# MecanumDrone_SchematicV1.net
KiCad netlist of a schematic drawn in EasyEDA Pro
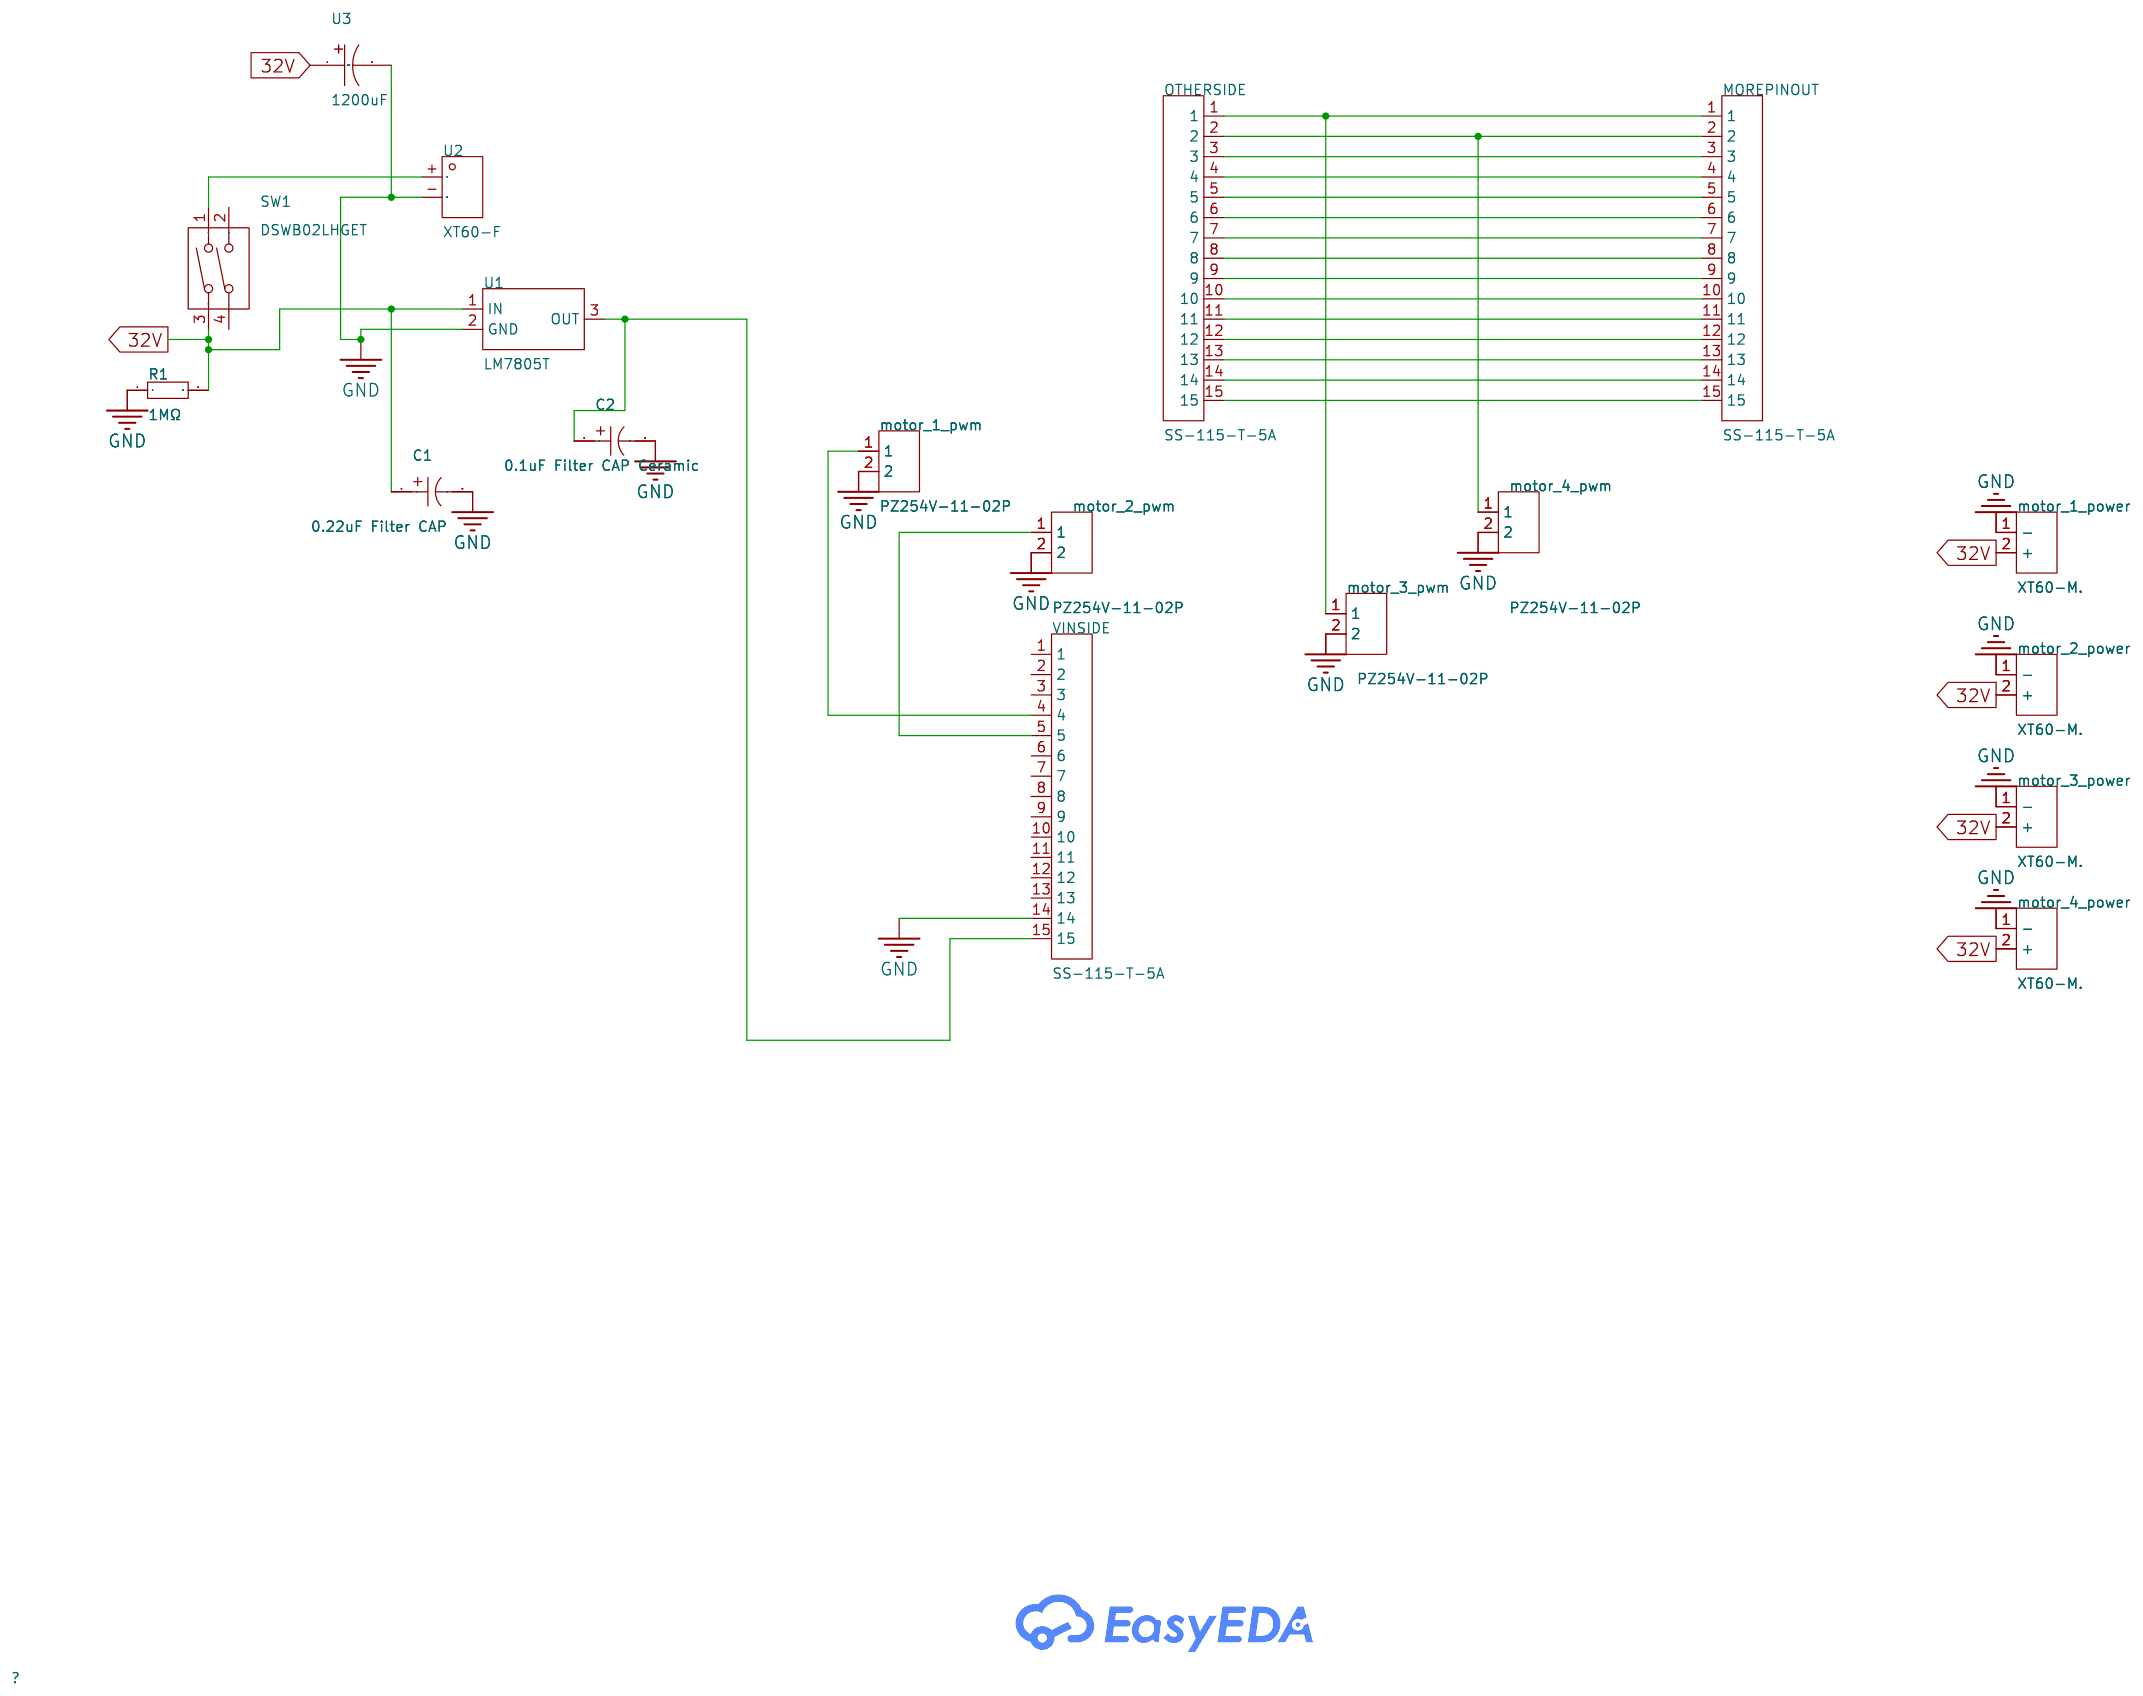
[diagram p0: schematic sheet]

(export (version "E")
  (design (tool "Eeschema 10.0.6"))
  (components
    (comp (ref "C1")
      (value "0.22uF Filter CAP")
      (footprint "easyedapro:CAP-TH_BD6.0-P2.50-D0.5-FD")
      (fields (field (name "Manufacturer Part") "KM1E101M0611") (field (name "Manufacturer") "ROQANG(容强)"))
      (libsource (lib "easyedapro") (part "KM1E101M0611"))
    )
    (comp (ref "C2")
      (value "0.1uF Filter CAP Ceramic")
      (footprint "easyedapro:CAP-TH_BD6.0-P2.50-D0.5-FD")
      (fields (field (name "Manufacturer Part") "KM1E101M0611") (field (name "Manufacturer") "ROQANG(容强)"))
      (libsource (lib "easyedapro") (part "KM1E101M0611"))
    )
    (comp (ref "MOREPINOUT")
      (value "SS-115-T-5A")
      (footprint "easyedapro:HDR-TH_15P-SS-115-T-5A")
      (fields (field (name "Manufacturer") "SAMTEC"))
      (libsource (lib "easyedapro") (part "SS-115-T-5A"))
    )
    (comp (ref "motor_1_power")
      (value "XT60-M.")
      (footprint "easyedapro:CONN-TH_XT60")
      (fields (field (name "Manufacturer") "AMASS(艾迈斯)"))
      (libsource (lib "easyedapro") (part "XT60"))
    )
    (comp (ref "motor_1_pwm")
      (value "PZ254V-11-02P")
      (footprint "easyedapro:HDR-TH_2P-P2.54-V-M")
      (fields (field (name "Manufacturer") "XFCN(兴飞)"))
      (libsource (lib "easyedapro") (part "PZ254V-11-02P"))
    )
    (comp (ref "motor_2_power")
      (value "XT60-M.")
      (footprint "easyedapro:CONN-TH_XT60")
      (fields (field (name "Manufacturer") "AMASS(艾迈斯)"))
      (libsource (lib "easyedapro") (part "XT60"))
    )
    (comp (ref "motor_2_pwm")
      (value "PZ254V-11-02P")
      (footprint "easyedapro:HDR-TH_2P-P2.54-V-M")
      (fields (field (name "Manufacturer") "XFCN(兴飞)"))
      (libsource (lib "easyedapro") (part "PZ254V-11-02P"))
    )
    (comp (ref "motor_3_power")
      (value "XT60-M.")
      (footprint "easyedapro:CONN-TH_XT60")
      (fields (field (name "Manufacturer") "AMASS(艾迈斯)"))
      (libsource (lib "easyedapro") (part "XT60"))
    )
    (comp (ref "motor_3_pwm")
      (value "PZ254V-11-02P")
      (footprint "easyedapro:HDR-TH_2P-P2.54-V-M")
      (fields (field (name "Manufacturer") "XFCN(兴飞)"))
      (libsource (lib "easyedapro") (part "PZ254V-11-02P"))
    )
    (comp (ref "motor_4_power")
      (value "XT60-M.")
      (footprint "easyedapro:CONN-TH_XT60")
      (fields (field (name "Manufacturer") "AMASS(艾迈斯)"))
      (libsource (lib "easyedapro") (part "XT60"))
    )
    (comp (ref "motor_4_pwm")
      (value "PZ254V-11-02P")
      (footprint "easyedapro:HDR-TH_2P-P2.54-V-M")
      (fields (field (name "Manufacturer") "XFCN(兴飞)"))
      (libsource (lib "easyedapro") (part "PZ254V-11-02P"))
    )
    (comp (ref "OTHERSIDE")
      (value "SS-115-T-5A")
      (footprint "easyedapro:HDR-TH_15P-SS-115-T-5A")
      (fields (field (name "Manufacturer") "SAMTEC"))
      (libsource (lib "easyedapro") (part "SS-115-T-5A"))
    )
    (comp (ref "R1")
      (value "1MΩ")
      (footprint "easyedapro:RES-TH_BD2.2-L6.5-P10.50-D0.6")
      (fields
        (field (name "Manufacturer Part") "RN1/2WS1MΩFT/BA1")
        (field (name "Manufacturer") "Tyohm(幸亚电阻)")
      )
      (libsource (lib "easyedapro") (part "RN1/2WS1MΩFT/BA1"))
    )
    (comp (ref "SW1")
      (value "DSWB02LHGET")
      (footprint "easyedapro:SW-TH_DSWB02LHGET")
      (description "Type:Slide, Rocked Circuit:SPST Number of Positions:2 Lead Pitch:2.54mm Operating Life:- Color:Red")
      (fields (field (name "Manufacturer") "YE"))
      (libsource (lib "easyedapro") (part "DSWB02LHGET"))
    )
    (comp (ref "U1")
      (value "LM7805T")
      (footprint "easyedapro:TO-220-3_L10.0-W4.5-P2.54-L-1")
      (fields (field (name "Manufacturer") "HTC"))
      (libsource (lib "easyedapro") (part "LM7805T_C36350857"))
    )
    (comp (ref "U2")
      (value "XT60-F")
      (footprint "easyedapro:CONN-TH_XT60PB-F")
      (fields (field (name "Manufacturer") "AMASS(艾迈斯)"))
      (libsource (lib "easyedapro") (part "XT60-F"))
    )
    (comp (ref "U3")
      (value "1200uF")
      (footprint "easyedapro:CAP-TH_BD30.0-P10.00-D2.3-FD")
      (fields (field (name "Manufacturer Part") "B43305B2128M67") (field (name "Manufacturer") "TDK"))
      (libsource (lib "easyedapro") (part "B43305B2128M67"))
    )
    (comp (ref "VINSIDE")
      (value "SS-115-T-5A")
      (footprint "easyedapro:HDR-TH_15P-SS-115-T-5A")
      (fields (field (name "Manufacturer") "SAMTEC"))
      (libsource (lib "easyedapro") (part "SS-115-T-5A"))
    )
  )
  (nets
    (net (code "1") (name "32V") (class "Default")
      (node (ref "C1") (pin "1") (pinfunction "1_1") (pintype "input"))
      (node (ref "R1") (pin "2") (pinfunction "2_2") (pintype "unspecified"))
      (node (ref "SW1") (pin "3") (pinfunction "3_3") (pintype "unspecified"))
      (node (ref "U1") (pin "1") (pinfunction "IN_1") (pintype "unspecified"))
      (node (ref "U3") (pin "1") (pinfunction "1_1") (pintype "unspecified"))
      (node (ref "motor_1_power") (pin "2") (pinfunction "+_2") (pintype "unspecified"))
      (node (ref "motor_2_power") (pin "2") (pinfunction "+_2") (pintype "unspecified"))
      (node (ref "motor_3_power") (pin "2") (pinfunction "+_2") (pintype "unspecified"))
      (node (ref "motor_4_power") (pin "2") (pinfunction "+_2") (pintype "unspecified"))
    )
    (net (code "2") (name "GND") (class "Default")
      (node (ref "C1") (pin "2") (pinfunction "2_2") (pintype "input"))
      (node (ref "C2") (pin "2") (pinfunction "2_2") (pintype "input"))
      (node (ref "R1") (pin "1") (pinfunction "1_1") (pintype "unspecified"))
      (node (ref "U1") (pin "2") (pinfunction "GND_2") (pintype "unspecified"))
      (node (ref "U2") (pin "-") (pinfunction "2_-") (pintype "input"))
      (node (ref "U3") (pin "2") (pinfunction "2_2") (pintype "unspecified"))
      (node (ref "VINSIDE") (pin "14") (pinfunction "14_14") (pintype "unspecified"))
      (node (ref "motor_1_power") (pin "1") (pinfunction "-_1") (pintype "unspecified"))
      (node (ref "motor_1_pwm") (pin "2") (pinfunction "2_2") (pintype "unspecified"))
      (node (ref "motor_2_power") (pin "1") (pinfunction "-_1") (pintype "unspecified"))
      (node (ref "motor_2_pwm") (pin "2") (pinfunction "2_2") (pintype "unspecified"))
      (node (ref "motor_3_power") (pin "1") (pinfunction "-_1") (pintype "unspecified"))
      (node (ref "motor_3_pwm") (pin "2") (pinfunction "2_2") (pintype "unspecified"))
      (node (ref "motor_4_power") (pin "1") (pinfunction "-_1") (pintype "unspecified"))
      (node (ref "motor_4_pwm") (pin "2") (pinfunction "2_2") (pintype "unspecified"))
    )
    (net (code "3") (name "Net-(MOREPINOUT-Pad1)") (class "Default")
      (node (ref "MOREPINOUT") (pin "1") (pinfunction "1_1") (pintype "unspecified"))
      (node (ref "OTHERSIDE") (pin "1") (pinfunction "1_1") (pintype "unspecified"))
      (node (ref "motor_3_pwm") (pin "1") (pinfunction "1_1") (pintype "unspecified"))
    )
    (net (code "4") (name "Net-(MOREPINOUT-Pad2)") (class "Default")
      (node (ref "MOREPINOUT") (pin "2") (pinfunction "2_2") (pintype "unspecified"))
      (node (ref "OTHERSIDE") (pin "2") (pinfunction "2_2") (pintype "unspecified"))
      (node (ref "motor_4_pwm") (pin "1") (pinfunction "1_1") (pintype "unspecified"))
    )
    (net (code "5") (name "Net-(MOREPINOUT-Pad3)") (class "Default")
      (node (ref "MOREPINOUT") (pin "3") (pinfunction "3_3") (pintype "unspecified"))
      (node (ref "OTHERSIDE") (pin "3") (pinfunction "3_3") (pintype "unspecified"))
    )
    (net (code "6") (name "Net-(MOREPINOUT-Pad4)") (class "Default")
      (node (ref "MOREPINOUT") (pin "4") (pinfunction "4_4") (pintype "unspecified"))
      (node (ref "OTHERSIDE") (pin "4") (pinfunction "4_4") (pintype "unspecified"))
    )
    (net (code "7") (name "Net-(MOREPINOUT-Pad5)") (class "Default")
      (node (ref "MOREPINOUT") (pin "5") (pinfunction "5_5") (pintype "unspecified"))
      (node (ref "OTHERSIDE") (pin "5") (pinfunction "5_5") (pintype "unspecified"))
    )
    (net (code "8") (name "Net-(MOREPINOUT-Pad6)") (class "Default")
      (node (ref "MOREPINOUT") (pin "6") (pinfunction "6_6") (pintype "unspecified"))
      (node (ref "OTHERSIDE") (pin "6") (pinfunction "6_6") (pintype "unspecified"))
    )
    (net (code "9") (name "Net-(MOREPINOUT-Pad7)") (class "Default")
      (node (ref "MOREPINOUT") (pin "7") (pinfunction "7_7") (pintype "unspecified"))
      (node (ref "OTHERSIDE") (pin "7") (pinfunction "7_7") (pintype "unspecified"))
    )
    (net (code "10") (name "Net-(MOREPINOUT-Pad8)") (class "Default")
      (node (ref "MOREPINOUT") (pin "8") (pinfunction "8_8") (pintype "unspecified"))
      (node (ref "OTHERSIDE") (pin "8") (pinfunction "8_8") (pintype "unspecified"))
    )
    (net (code "11") (name "Net-(MOREPINOUT-Pad9)") (class "Default")
      (node (ref "MOREPINOUT") (pin "9") (pinfunction "9_9") (pintype "unspecified"))
      (node (ref "OTHERSIDE") (pin "9") (pinfunction "9_9") (pintype "unspecified"))
    )
    (net (code "12") (name "Net-(MOREPINOUT-Pad10)") (class "Default")
      (node (ref "MOREPINOUT") (pin "10") (pinfunction "10_10") (pintype "unspecified"))
      (node (ref "OTHERSIDE") (pin "10") (pinfunction "10_10") (pintype "unspecified"))
    )
    (net (code "13") (name "Net-(MOREPINOUT-Pad11)") (class "Default")
      (node (ref "MOREPINOUT") (pin "11") (pinfunction "11_11") (pintype "unspecified"))
      (node (ref "OTHERSIDE") (pin "11") (pinfunction "11_11") (pintype "unspecified"))
    )
    (net (code "14") (name "Net-(MOREPINOUT-Pad12)") (class "Default")
      (node (ref "MOREPINOUT") (pin "12") (pinfunction "12_12") (pintype "unspecified"))
      (node (ref "OTHERSIDE") (pin "12") (pinfunction "12_12") (pintype "unspecified"))
    )
    (net (code "15") (name "Net-(MOREPINOUT-Pad13)") (class "Default")
      (node (ref "MOREPINOUT") (pin "13") (pinfunction "13_13") (pintype "unspecified"))
      (node (ref "OTHERSIDE") (pin "13") (pinfunction "13_13") (pintype "unspecified"))
    )
    (net (code "16") (name "Net-(MOREPINOUT-Pad14)") (class "Default")
      (node (ref "MOREPINOUT") (pin "14") (pinfunction "14_14") (pintype "unspecified"))
      (node (ref "OTHERSIDE") (pin "14") (pinfunction "14_14") (pintype "unspecified"))
    )
    (net (code "17") (name "Net-(MOREPINOUT-Pad15)") (class "Default")
      (node (ref "MOREPINOUT") (pin "15") (pinfunction "15_15") (pintype "unspecified"))
      (node (ref "OTHERSIDE") (pin "15") (pinfunction "15_15") (pintype "unspecified"))
    )
    (net (code "18") (name "Net-(U1-OUT)") (class "Default")
      (node (ref "C2") (pin "1") (pinfunction "1_1") (pintype "input"))
      (node (ref "U1") (pin "3") (pinfunction "OUT_3") (pintype "unspecified"))
      (node (ref "VINSIDE") (pin "15") (pinfunction "15_15") (pintype "unspecified"))
    )
    (net (code "19") (name "Net-(U2-1)") (class "Default")
      (node (ref "SW1") (pin "1") (pinfunction "1_1") (pintype "unspecified"))
      (node (ref "U2") (pin "+") (pinfunction "1_+") (pintype "input"))
    )
    (net (code "20") (name "Net-(VINSIDE-Pad4)") (class "Default")
      (node (ref "VINSIDE") (pin "4") (pinfunction "4_4") (pintype "unspecified"))
      (node (ref "motor_1_pwm") (pin "1") (pinfunction "1_1") (pintype "unspecified"))
    )
    (net (code "21") (name "Net-(VINSIDE-Pad5)") (class "Default")
      (node (ref "VINSIDE") (pin "5") (pinfunction "5_5") (pintype "unspecified"))
      (node (ref "motor_2_pwm") (pin "1") (pinfunction "1_1") (pintype "unspecified"))
    )
    (net (code "22") (name "unconnected-(SW1-Pad2)") (class "Default")
      (node (ref "SW1") (pin "2") (pinfunction "2_2") (pintype "unspecified"))
    )
    (net (code "23") (name "unconnected-(SW1-Pad4)") (class "Default")
      (node (ref "SW1") (pin "4") (pinfunction "4_4") (pintype "unspecified"))
    )
    (net (code "24") (name "unconnected-(VINSIDE-Pad1)") (class "Default")
      (node (ref "VINSIDE") (pin "1") (pinfunction "1_1") (pintype "unspecified"))
    )
    (net (code "25") (name "unconnected-(VINSIDE-Pad2)") (class "Default")
      (node (ref "VINSIDE") (pin "2") (pinfunction "2_2") (pintype "unspecified"))
    )
    (net (code "26") (name "unconnected-(VINSIDE-Pad3)") (class "Default")
      (node (ref "VINSIDE") (pin "3") (pinfunction "3_3") (pintype "unspecified"))
    )
    (net (code "27") (name "unconnected-(VINSIDE-Pad6)") (class "Default")
      (node (ref "VINSIDE") (pin "6") (pinfunction "6_6") (pintype "unspecified"))
    )
    (net (code "28") (name "unconnected-(VINSIDE-Pad7)") (class "Default")
      (node (ref "VINSIDE") (pin "7") (pinfunction "7_7") (pintype "unspecified"))
    )
    (net (code "29") (name "unconnected-(VINSIDE-Pad8)") (class "Default")
      (node (ref "VINSIDE") (pin "8") (pinfunction "8_8") (pintype "unspecified"))
    )
    (net (code "30") (name "unconnected-(VINSIDE-Pad9)") (class "Default")
      (node (ref "VINSIDE") (pin "9") (pinfunction "9_9") (pintype "unspecified"))
    )
    (net (code "31") (name "unconnected-(VINSIDE-Pad10)") (class "Default")
      (node (ref "VINSIDE") (pin "10") (pinfunction "10_10") (pintype "unspecified"))
    )
    (net (code "32") (name "unconnected-(VINSIDE-Pad11)") (class "Default")
      (node (ref "VINSIDE") (pin "11") (pinfunction "11_11") (pintype "unspecified"))
    )
    (net (code "33") (name "unconnected-(VINSIDE-Pad12)") (class "Default")
      (node (ref "VINSIDE") (pin "12") (pinfunction "12_12") (pintype "unspecified"))
    )
    (net (code "34") (name "unconnected-(VINSIDE-Pad13)") (class "Default")
      (node (ref "VINSIDE") (pin "13") (pinfunction "13_13") (pintype "unspecified"))
    )
  )
)
